# 05_RTCvsMMC.net
KiCad netlist of a schematic drawn in Altium Designer
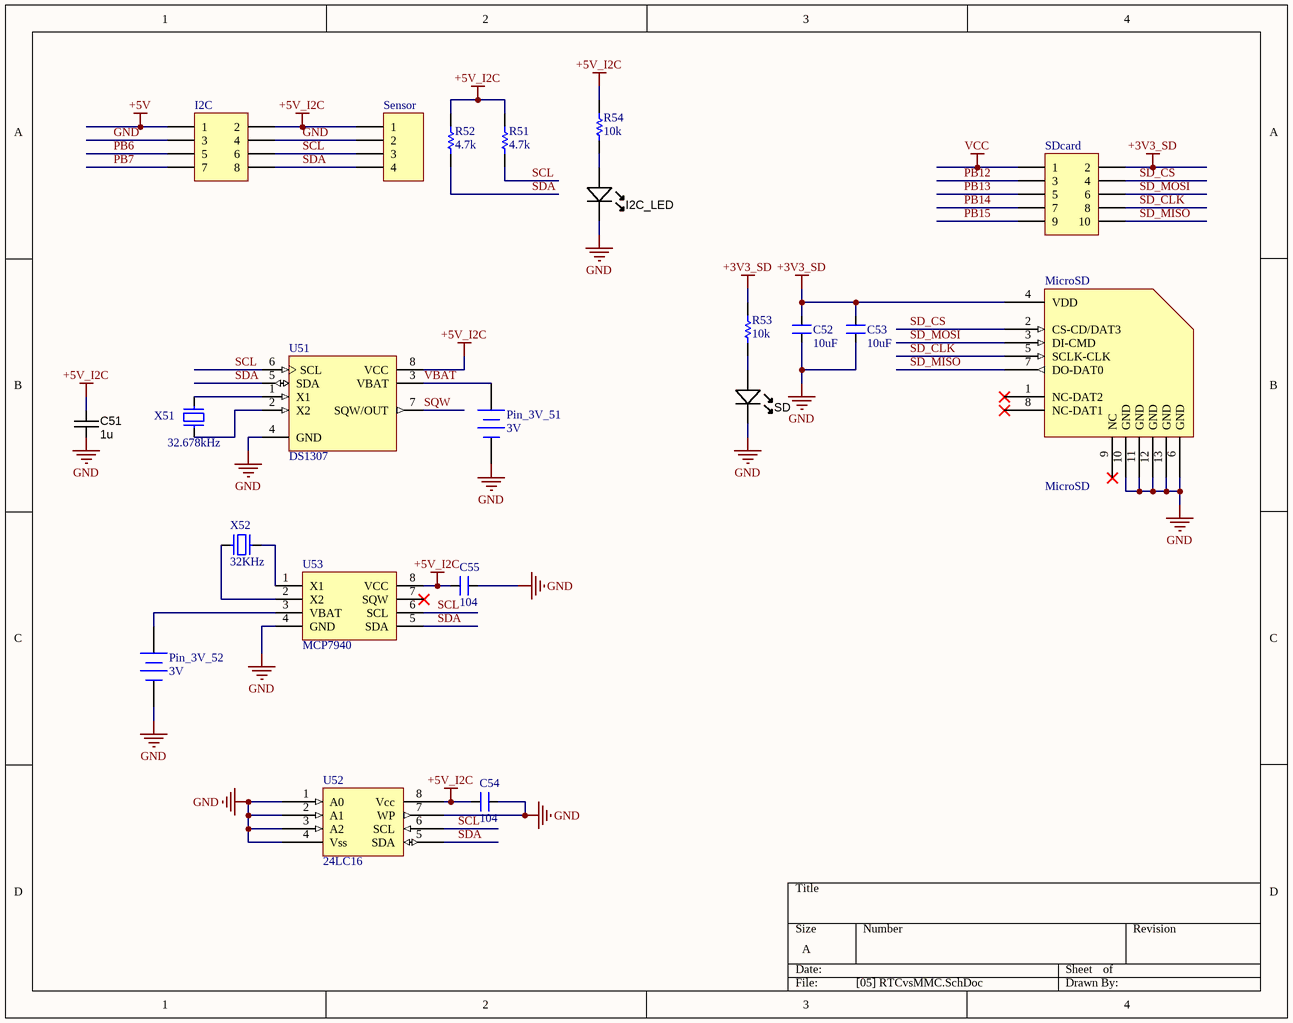
[diagram p0: [05] RTCvsMMC.SchDoc]

(export (version "E")
  (design (tool "Eeschema 10.0.6"))
  (components
    (comp (ref "C51")
      (value "1u")
      (footprint "CAPC1608N")
      (description "Capacitor SMD Cer 1nF 10% 100V X7R 0603")
      (fields (field (name "TOLERANCE") "±10%") (field (name "Comment") "approved sub OK"))
      (libsource (lib "PBL - Capacitors") (part "CAPC_1n_0603_100V"))
    )
    (comp (ref "C52")
      (value "10uF")
      (footprint "CAPC2012N_F")
      (fields (field (name "Comment") "CAP NP"))
      (libsource (lib "Tuan") (part "CAP NP"))
    )
    (comp (ref "C53")
      (value "10uF")
      (footprint "CAPC2012N_F")
      (fields (field (name "Comment") "CAP NP"))
      (libsource (lib "Tuan") (part "CAP NP"))
    )
    (comp (ref "C54")
      (value "104")
      (footprint "CAPC2012N_F")
      (fields (field (name "Comment") "CAP NP"))
      (libsource (lib "Tuan") (part "CAP NP"))
    )
    (comp (ref "C55")
      (value "104")
      (footprint "CAPC2012N_F")
      (fields (field (name "Comment") "CAP NP"))
      (libsource (lib "Tuan") (part "CAP NP"))
    )
    (comp (ref "I2C")
      (value "Header 4X2")
      (footprint "HDR2X4")
      (description "Header, 4-Pin, Dual row")
      (fields (field (name "PUBLISHER") "Altium Limited"))
      (libsource (lib "Miscellaneous Connectors") (part "Header 4X2"))
    )
    (comp (ref "I2C_LED")
      (value "Green")
      (footprint "LED-0805-K")
      (description "LED, 0805 SMD, Green")
      (libsource (lib "PBL - Light Sources") (part "LED_SMD_Green_0805"))
    )
    (comp (ref "MicroSD") (value "MicroSD") (footprint "microsd") (libsource (lib "Tuan") (part "MicroSD")))
    (comp (ref "Pin_3V_51")
      (value "3V")
      (footprint "CR1220")
      (description "Multicell Battery")
      (fields (field (name "PUBLISHER") "Altium Limited"))
      (libsource (lib "heromap") (part "Battery"))
    )
    (comp (ref "Pin_3V_52")
      (value "3V")
      (footprint "CR1220")
      (description "Multicell Battery")
      (fields (field (name "PUBLISHER") "Altium Limited"))
      (libsource (lib "heromap") (part "Battery"))
    )
    (comp (ref "R51")
      (value "4.7k")
      (footprint "RESC1608N_ZERO")
      (fields (field (name "Comment") "Res"))
      (libsource (lib "Tuan") (part "Res"))
    )
    (comp (ref "R52")
      (value "4.7k")
      (footprint "RESC1608N_ZERO")
      (fields (field (name "Comment") "Res"))
      (libsource (lib "Tuan") (part "Res"))
    )
    (comp (ref "R53")
      (value "10k")
      (footprint "RESC1608N_ZERO")
      (fields (field (name "Comment") "Res"))
      (libsource (lib "Tuan") (part "Res"))
    )
    (comp (ref "R54")
      (value "10k")
      (footprint "RESC1608N_ZERO")
      (fields (field (name "Comment") "Res"))
      (libsource (lib "Tuan") (part "Res"))
    )
    (comp (ref "SD")
      (value "Green")
      (footprint "LED-0805-K")
      (description "LED, 0805 SMD, Green")
      (libsource (lib "PBL - Light Sources") (part "LED_SMD_Green_0805"))
    )
    (comp (ref "SDcard")
      (value "Header 5X2")
      (footprint "HDR2X5")
      (description "Header, 5-Pin, Dual row")
      (fields (field (name "PUBLISHER") "Altium Limited"))
      (libsource (lib "Miscellaneous Connectors") (part "Header 5X2"))
    )
    (comp (ref "Sensor")
      (value "Header 4")
      (footprint "HDR1X4")
      (description "Header, 4-Pin")
      (fields (field (name "PUBLISHER") "Altium Limited"))
      (libsource (lib "Miscellaneous Connectors") (part "Header 4"))
    )
    (comp (ref "U51")
      (value "DS1307")
      (footprint "SOIC127P600X175-8AN")
      (libsource (lib "Tuan") (part "DS1307"))
    )
    (comp (ref "U52")
      (value "24LC16")
      (footprint "SOIC-8")
      (libsource (lib "PhamTu_IntLib") (part "24LC04B"))
    )
    (comp (ref "U53")
      (value "MCP7940")
      (footprint "SOIC-8")
      (description "Real Timer Serial")
      (libsource (lib "MLab Miscellaneous Devices") (part "DS1307"))
    )
    (comp (ref "X51") (value "32.678kHz") (footprint "XTminiv2") (libsource (lib "Tuan") (part "Crystal")))
    (comp (ref "X52")
      (value "32KHz")
      (footprint "XTminiv2")
      (description "Crystal For all Crystal 2pin.")
      (libsource (lib "syhaunguyen") (part "XT2"))
    )
  )
  (nets
    (net (code "1") (name "+3V3_SD") (class "Default")
      (node (ref "C52") (pin "2") (pinfunction "2_2") (pintype "passive"))
      (node (ref "C53") (pin "2") (pinfunction "2_2") (pintype "passive"))
      (node (ref "MicroSD") (pin "4") (pinfunction "VDD_4") (pintype "passive"))
      (node (ref "R53") (pin "2") (pinfunction "2_2") (pintype "passive"))
      (node (ref "SDcard") (pin "2") (pinfunction "2_2") (pintype "passive"))
    )
    (net (code "2") (name "+5V") (class "Default")
      (node (ref "I2C") (pin "1") (pinfunction "1_1") (pintype "passive"))
    )
    (net (code "3") (name "+5V_I2C") (class "Default")
      (node (ref "C51") (pin "1") (pintype "passive"))
      (node (ref "C54") (pin "1") (pinfunction "1_1") (pintype "passive"))
      (node (ref "C55") (pin "1") (pinfunction "1_1") (pintype "passive"))
      (node (ref "I2C") (pin "2") (pinfunction "2_2") (pintype "passive"))
      (node (ref "R51") (pin "2") (pinfunction "2_2") (pintype "passive"))
      (node (ref "R52") (pin "2") (pinfunction "2_2") (pintype "passive"))
      (node (ref "R54") (pin "2") (pinfunction "2_2") (pintype "passive"))
      (node (ref "Sensor") (pin "1") (pinfunction "1_1") (pintype "passive"))
      (node (ref "U51") (pin "8") (pinfunction "VCC_8") (pintype "power_in"))
      (node (ref "U52") (pin "8") (pinfunction "Vcc_8") (pintype "power_in"))
      (node (ref "U53") (pin "8") (pinfunction "VCC_8") (pintype "passive"))
    )
    (net (code "4") (name "/PB6") (class "Default")
      (node (ref "I2C") (pin "5") (pinfunction "5_5") (pintype "passive"))
    )
    (net (code "5") (name "/PB7") (class "Default")
      (node (ref "I2C") (pin "7") (pinfunction "7_7") (pintype "passive"))
    )
    (net (code "6") (name "/PB12") (class "Default")
      (node (ref "SDcard") (pin "3") (pinfunction "3_3") (pintype "passive"))
    )
    (net (code "7") (name "/PB13") (class "Default")
      (node (ref "SDcard") (pin "5") (pinfunction "5_5") (pintype "passive"))
    )
    (net (code "8") (name "/PB14") (class "Default")
      (node (ref "SDcard") (pin "7") (pinfunction "7_7") (pintype "passive"))
    )
    (net (code "9") (name "/PB15") (class "Default")
      (node (ref "SDcard") (pin "9") (pinfunction "9_9") (pintype "passive"))
    )
    (net (code "10") (name "/SCL") (class "Default")
      (node (ref "I2C") (pin "6") (pinfunction "6_6") (pintype "passive"))
      (node (ref "R51") (pin "1") (pinfunction "1_1") (pintype "passive"))
      (node (ref "Sensor") (pin "3") (pinfunction "3_3") (pintype "passive"))
      (node (ref "U51") (pin "6") (pinfunction "SCL_6") (pintype "input"))
      (node (ref "U52") (pin "6") (pinfunction "SCL_6") (pintype "input"))
      (node (ref "U53") (pin "6") (pinfunction "SCL_6") (pintype "passive"))
    )
    (net (code "11") (name "/SDA") (class "Default")
      (node (ref "I2C") (pin "8") (pinfunction "8_8") (pintype "passive"))
      (node (ref "R52") (pin "1") (pinfunction "1_1") (pintype "passive"))
      (node (ref "Sensor") (pin "4") (pinfunction "4_4") (pintype "passive"))
      (node (ref "U51") (pin "5") (pinfunction "SDA_5") (pintype "bidirectional"))
      (node (ref "U52") (pin "5") (pinfunction "SDA_5") (pintype "bidirectional"))
      (node (ref "U53") (pin "5") (pinfunction "SDA_5") (pintype "passive"))
    )
    (net (code "12") (name "/SD_CLK") (class "Default")
      (node (ref "MicroSD") (pin "5") (pinfunction "SCLK-CLK_5") (pintype "input"))
      (node (ref "SDcard") (pin "8") (pinfunction "8_8") (pintype "passive"))
    )
    (net (code "13") (name "/SD_CS") (class "Default")
      (node (ref "MicroSD") (pin "2") (pinfunction "CS-CD/DAT3_2") (pintype "input"))
      (node (ref "SDcard") (pin "4") (pinfunction "4_4") (pintype "passive"))
    )
    (net (code "14") (name "/SD_MISO") (class "Default")
      (node (ref "MicroSD") (pin "7") (pinfunction "DO-DAT0_7") (pintype "output"))
      (node (ref "SDcard") (pin "10") (pinfunction "10_10") (pintype "passive"))
    )
    (net (code "15") (name "/SD_MOSI") (class "Default")
      (node (ref "MicroSD") (pin "3") (pinfunction "DI-CMD_3") (pintype "input"))
      (node (ref "SDcard") (pin "6") (pinfunction "6_6") (pintype "passive"))
    )
    (net (code "16") (name "/SQW") (class "Default")
      (node (ref "U51") (pin "7") (pinfunction "SQW/OUT_7") (pintype "output"))
    )
    (net (code "17") (name "/VBAT") (class "Default")
      (node (ref "Pin_3V_51") (pin "1") (pinfunction "+_1") (pintype "passive"))
      (node (ref "U51") (pin "3") (pinfunction "VBAT_3") (pintype "power_in"))
    )
    (net (code "18") (name "GND") (class "Default")
      (node (ref "C51") (pin "2") (pintype "passive"))
      (node (ref "C52") (pin "1") (pinfunction "1_1") (pintype "passive"))
      (node (ref "C53") (pin "1") (pinfunction "1_1") (pintype "passive"))
      (node (ref "C54") (pin "2") (pinfunction "2_2") (pintype "passive"))
      (node (ref "C55") (pin "2") (pinfunction "2_2") (pintype "passive"))
      (node (ref "I2C") (pin "3") (pinfunction "3_3") (pintype "passive"))
      (node (ref "I2C") (pin "4") (pinfunction "4_4") (pintype "passive"))
      (node (ref "I2C_LED") (pin "K") (pinfunction "K_K") (pintype "passive"))
      (node (ref "MicroSD") (pin "10") (pinfunction "GND_10") (pintype "passive"))
      (node (ref "MicroSD") (pin "11") (pinfunction "GND_11") (pintype "passive"))
      (node (ref "MicroSD") (pin "12") (pinfunction "GND_12") (pintype "passive"))
      (node (ref "MicroSD") (pin "13") (pinfunction "GND_13") (pintype "passive"))
      (node (ref "MicroSD") (pin "6") (pinfunction "GND_6") (pintype "passive"))
      (node (ref "Pin_3V_51") (pin "2") (pinfunction "-_2") (pintype "passive"))
      (node (ref "Pin_3V_52") (pin "2") (pinfunction "-_2") (pintype "passive"))
      (node (ref "SD") (pin "K") (pinfunction "K_K") (pintype "passive"))
      (node (ref "Sensor") (pin "2") (pinfunction "2_2") (pintype "passive"))
      (node (ref "U51") (pin "4") (pinfunction "GND_4") (pintype "power_in"))
      (node (ref "U52") (pin "1") (pinfunction "A0_1") (pintype "input"))
      (node (ref "U52") (pin "2") (pinfunction "A1_2") (pintype "input"))
      (node (ref "U52") (pin "3") (pinfunction "A2_3") (pintype "input"))
      (node (ref "U52") (pin "4") (pinfunction "Vss_4") (pintype "power_in"))
      (node (ref "U52") (pin "7") (pinfunction "WP_7") (pintype "output"))
      (node (ref "U53") (pin "4") (pinfunction "GND_4") (pintype "passive"))
    )
    (net (code "19") (name "Net-(I2C_LED-PadA)") (class "Default")
      (node (ref "I2C_LED") (pin "A") (pinfunction "A_A") (pintype "passive"))
      (node (ref "R54") (pin "1") (pinfunction "1_1") (pintype "passive"))
    )
    (net (code "20") (name "Net-(Pin_3V_52-+)") (class "Default")
      (node (ref "Pin_3V_52") (pin "1") (pinfunction "+_1") (pintype "passive"))
      (node (ref "U53") (pin "3") (pinfunction "VBAT_3") (pintype "passive"))
    )
    (net (code "21") (name "Net-(R53-Pad1)") (class "Default")
      (node (ref "R53") (pin "1") (pinfunction "1_1") (pintype "passive"))
      (node (ref "SD") (pin "A") (pinfunction "A_A") (pintype "passive"))
    )
    (net (code "22") (name "Net-(U51-X1)") (class "Default")
      (node (ref "U51") (pin "1") (pinfunction "X1_1") (pintype "input"))
      (node (ref "X51") (pin "1") (pinfunction "1_1") (pintype "passive"))
    )
    (net (code "23") (name "Net-(U51-X2)") (class "Default")
      (node (ref "U51") (pin "2") (pinfunction "X2_2") (pintype "input"))
      (node (ref "X51") (pin "2") (pinfunction "2_2") (pintype "passive"))
    )
    (net (code "24") (name "Net-(U53-X1)") (class "Default")
      (node (ref "U53") (pin "1") (pinfunction "X1_1") (pintype "passive"))
      (node (ref "X52") (pin "1") (pinfunction "1_1") (pintype "passive"))
    )
    (net (code "25") (name "Net-(U53-X2)") (class "Default")
      (node (ref "U53") (pin "2") (pinfunction "X2_2") (pintype "passive"))
      (node (ref "X52") (pin "2") (pinfunction "2_2") (pintype "passive"))
    )
    (net (code "26") (name "VCC") (class "Default")
      (node (ref "SDcard") (pin "1") (pinfunction "1_1") (pintype "passive"))
    )
    (net (code "27") (name "unconnected-(MicroSD-NC-DAT1-Pad8)") (class "Default")
      (node (ref "MicroSD") (pin "8") (pinfunction "NC-DAT1_8") (pintype "passive+no_connect"))
    )
    (net (code "28") (name "unconnected-(MicroSD-NC-DAT2-Pad1)") (class "Default")
      (node (ref "MicroSD") (pin "1") (pinfunction "NC-DAT2_1") (pintype "passive+no_connect"))
    )
    (net (code "29") (name "unconnected-(MicroSD-NC-Pad9)") (class "Default")
      (node (ref "MicroSD") (pin "9") (pinfunction "NC_9") (pintype "passive+no_connect"))
    )
    (net (code "30") (name "unconnected-(U53-SQW-Pad7)") (class "Default")
      (node (ref "U53") (pin "7") (pinfunction "SQW_7") (pintype "passive+no_connect"))
    )
  )
)
